# ToolManger-15ports-schematic.net
KiCad netlist of a schematic drawn in EAGLE
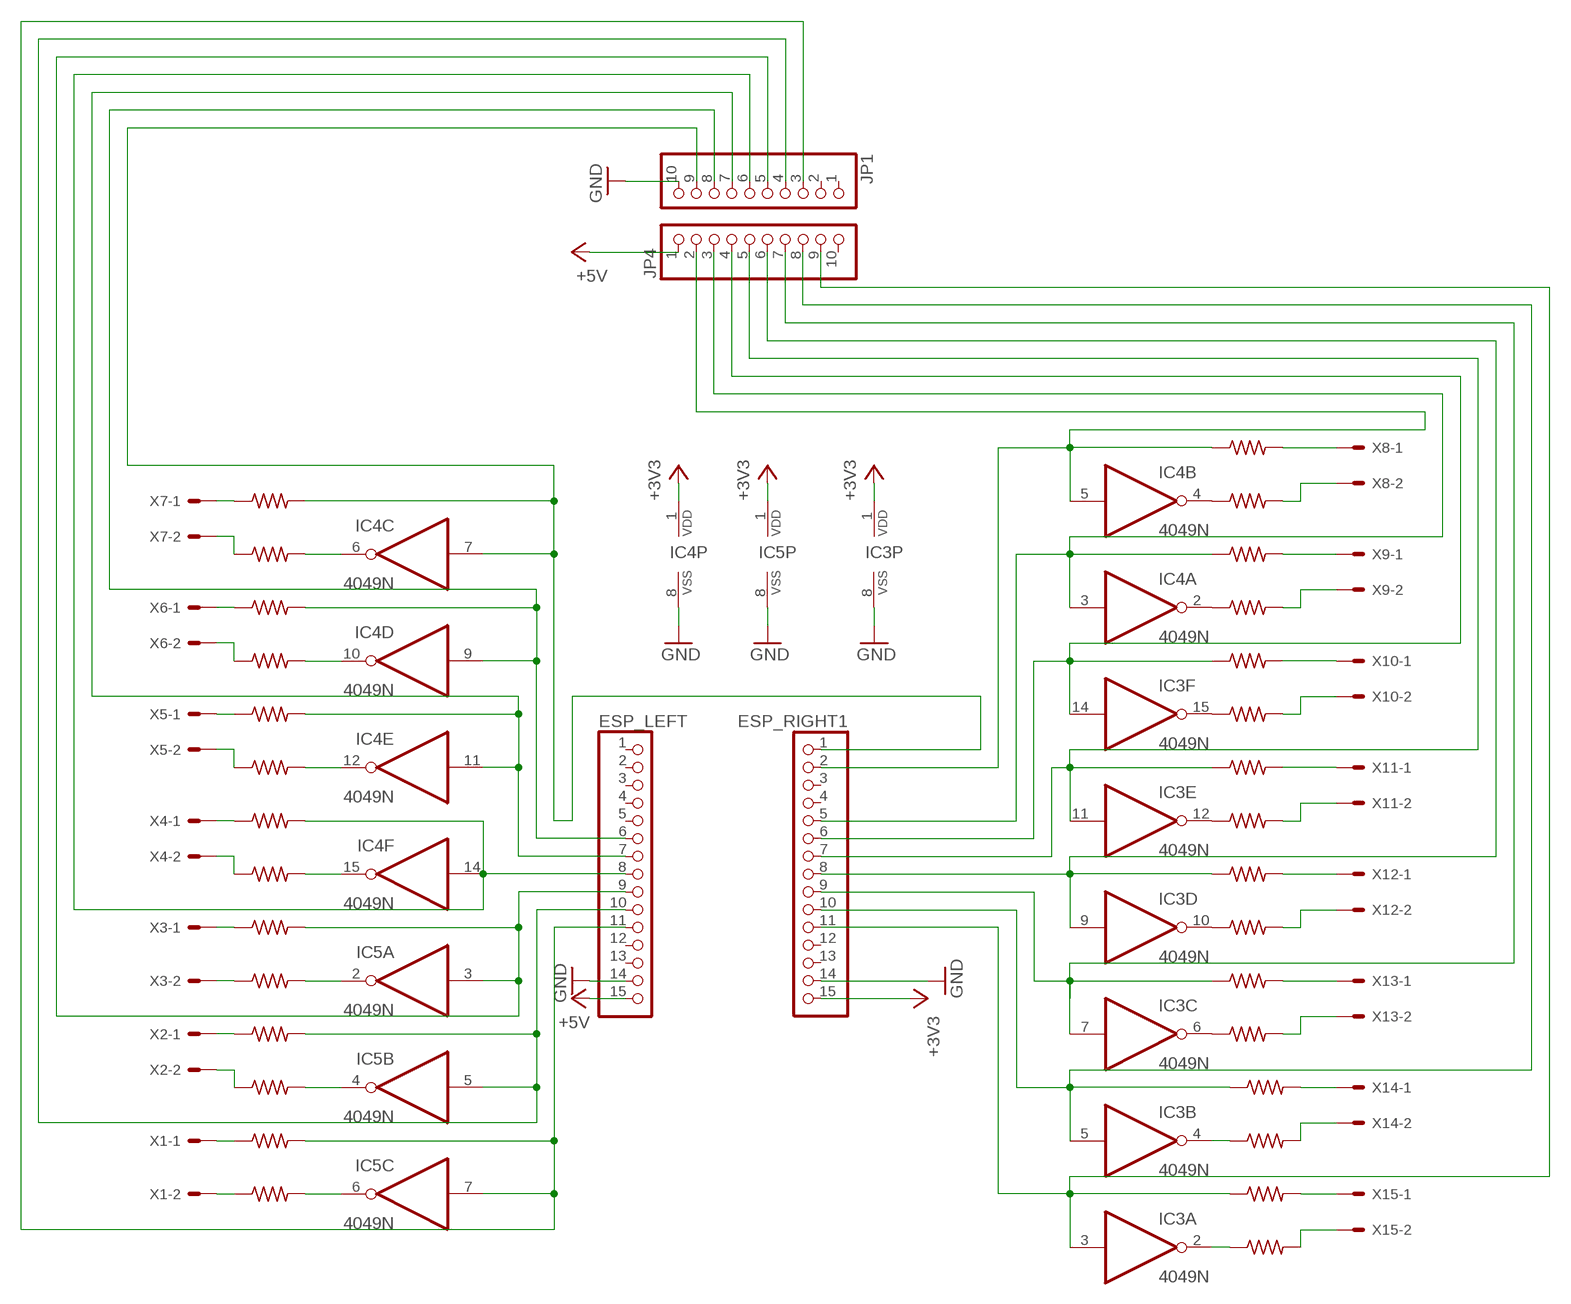
[diagram p0: schematic, sheet 1]

(export (version "E")
  (design (tool "Eeschema 10.0.6"))
  (components
    (comp (ref "ESP_LEFT")
      (value "PINHD-1X15")
      (footprint "eagle-import:1X15")
      (libsource (lib "eagle-import") (part "PINHD-1X15"))
    )
    (comp (ref "ESP_RIGHT1")
      (value "PINHD-1X15")
      (footprint "eagle-import:1X15")
      (libsource (lib "eagle-import") (part "PINHD-1X15"))
    )
    (comp (ref "IC3")
      (value "4049N")
      (footprint "eagle-import:DIL16")
      (libsource (lib "eagle-import") (part "4049N"))
    )
    (comp (ref "IC4")
      (value "4049N")
      (footprint "eagle-import:DIL16")
      (libsource (lib "eagle-import") (part "4049N"))
    )
    (comp (ref "IC5")
      (value "4049N")
      (footprint "eagle-import:DIL16")
      (libsource (lib "eagle-import") (part "4049N"))
    )
    (comp (ref "JP1")
      (value "PINHD-1X10")
      (footprint "eagle-import:1X10")
      (libsource (lib "eagle-import") (part "PINHD-1X10"))
    )
    (comp (ref "JP4")
      (value "PINHD-1X10")
      (footprint "eagle-import:1X10")
      (libsource (lib "eagle-import") (part "PINHD-1X10"))
    )
    (comp (ref "R1")
      (value "R-US_0207/12")
      (footprint "eagle-import:0207_12")
      (libsource (lib "eagle-import") (part "R-US_0207/12"))
    )
    (comp (ref "R2")
      (value "R-US_0207/12")
      (footprint "eagle-import:0207_12")
      (libsource (lib "eagle-import") (part "R-US_0207/12"))
    )
    (comp (ref "R3")
      (value "R-US_0207/12")
      (footprint "eagle-import:0207_12")
      (libsource (lib "eagle-import") (part "R-US_0207/12"))
    )
    (comp (ref "R4")
      (value "R-US_0207/12")
      (footprint "eagle-import:0207_12")
      (libsource (lib "eagle-import") (part "R-US_0207/12"))
    )
    (comp (ref "R5")
      (value "R-US_0207/12")
      (footprint "eagle-import:0207_12")
      (libsource (lib "eagle-import") (part "R-US_0207/12"))
    )
    (comp (ref "R6")
      (value "R-US_0207/12")
      (footprint "eagle-import:0207_12")
      (libsource (lib "eagle-import") (part "R-US_0207/12"))
    )
    (comp (ref "R7")
      (value "R-US_0207/12")
      (footprint "eagle-import:0207_12")
      (libsource (lib "eagle-import") (part "R-US_0207/12"))
    )
    (comp (ref "R8")
      (value "R-US_0207/12")
      (footprint "eagle-import:0207_12")
      (libsource (lib "eagle-import") (part "R-US_0207/12"))
    )
    (comp (ref "R9")
      (value "R-US_0207/12")
      (footprint "eagle-import:0207_12")
      (libsource (lib "eagle-import") (part "R-US_0207/12"))
    )
    (comp (ref "R10")
      (value "R-US_0207/12")
      (footprint "eagle-import:0207_12")
      (libsource (lib "eagle-import") (part "R-US_0207/12"))
    )
    (comp (ref "R11")
      (value "R-US_0207/12")
      (footprint "eagle-import:0207_12")
      (libsource (lib "eagle-import") (part "R-US_0207/12"))
    )
    (comp (ref "R12")
      (value "R-US_0207/12")
      (footprint "eagle-import:0207_12")
      (libsource (lib "eagle-import") (part "R-US_0207/12"))
    )
    (comp (ref "R13")
      (value "R-US_0207/12")
      (footprint "eagle-import:0207_12")
      (libsource (lib "eagle-import") (part "R-US_0207/12"))
    )
    (comp (ref "R14")
      (value "R-US_0207/12")
      (footprint "eagle-import:0207_12")
      (libsource (lib "eagle-import") (part "R-US_0207/12"))
    )
    (comp (ref "R15")
      (value "R-US_0207/12")
      (footprint "eagle-import:0207_12")
      (libsource (lib "eagle-import") (part "R-US_0207/12"))
    )
    (comp (ref "R16")
      (value "R-US_0207/12")
      (footprint "eagle-import:0207_12")
      (libsource (lib "eagle-import") (part "R-US_0207/12"))
    )
    (comp (ref "R17")
      (value "R-US_0207/12")
      (footprint "eagle-import:0207_12")
      (libsource (lib "eagle-import") (part "R-US_0207/12"))
    )
    (comp (ref "R18")
      (value "R-US_0207/12")
      (footprint "eagle-import:0207_12")
      (libsource (lib "eagle-import") (part "R-US_0207/12"))
    )
    (comp (ref "R19")
      (value "R-US_0207/12")
      (footprint "eagle-import:0207_12")
      (libsource (lib "eagle-import") (part "R-US_0207/12"))
    )
    (comp (ref "R21")
      (value "R-US_0207/12")
      (footprint "eagle-import:0207_12")
      (libsource (lib "eagle-import") (part "R-US_0207/12"))
    )
    (comp (ref "R22")
      (value "R-US_0207/12")
      (footprint "eagle-import:0207_12")
      (libsource (lib "eagle-import") (part "R-US_0207/12"))
    )
    (comp (ref "R23")
      (value "R-US_0207/12")
      (footprint "eagle-import:0207_12")
      (libsource (lib "eagle-import") (part "R-US_0207/12"))
    )
    (comp (ref "R24")
      (value "R-US_0207/12")
      (footprint "eagle-import:0207_12")
      (libsource (lib "eagle-import") (part "R-US_0207/12"))
    )
    (comp (ref "R25")
      (value "R-US_0207/12")
      (footprint "eagle-import:0207_12")
      (libsource (lib "eagle-import") (part "R-US_0207/12"))
    )
    (comp (ref "R26")
      (value "R-US_0207/12")
      (footprint "eagle-import:0207_12")
      (libsource (lib "eagle-import") (part "R-US_0207/12"))
    )
    (comp (ref "R27")
      (value "R-US_0207/12")
      (footprint "eagle-import:0207_12")
      (libsource (lib "eagle-import") (part "R-US_0207/12"))
    )
    (comp (ref "R28")
      (value "R-US_0207/12")
      (footprint "eagle-import:0207_12")
      (libsource (lib "eagle-import") (part "R-US_0207/12"))
    )
    (comp (ref "R29")
      (value "R-US_0207/12")
      (footprint "eagle-import:0207_12")
      (libsource (lib "eagle-import") (part "R-US_0207/12"))
    )
    (comp (ref "R30")
      (value "R-US_0207/12")
      (footprint "eagle-import:0207_12")
      (libsource (lib "eagle-import") (part "R-US_0207/12"))
    )
    (comp (ref "R32")
      (value "R-US_0207/12")
      (footprint "eagle-import:0207_12")
      (libsource (lib "eagle-import") (part "R-US_0207/12"))
    )
    (comp (ref "X1")
      (value "KK-156-2")
      (footprint "eagle-import:KK-156-2")
      (fields (field (name "MF") "MOLEX"))
      (libsource (lib "eagle-import") (part "KK-156-2"))
    )
    (comp (ref "X2")
      (value "KK-156-2")
      (footprint "eagle-import:KK-156-2")
      (fields (field (name "MF") "MOLEX"))
      (libsource (lib "eagle-import") (part "KK-156-2"))
    )
    (comp (ref "X3")
      (value "KK-156-2")
      (footprint "eagle-import:KK-156-2")
      (fields (field (name "MF") "MOLEX"))
      (libsource (lib "eagle-import") (part "KK-156-2"))
    )
    (comp (ref "X4")
      (value "KK-156-2")
      (footprint "eagle-import:KK-156-2")
      (fields (field (name "MF") "MOLEX"))
      (libsource (lib "eagle-import") (part "KK-156-2"))
    )
    (comp (ref "X5")
      (value "KK-156-2")
      (footprint "eagle-import:KK-156-2")
      (fields (field (name "MF") "MOLEX"))
      (libsource (lib "eagle-import") (part "KK-156-2"))
    )
    (comp (ref "X6")
      (value "KK-156-2")
      (footprint "eagle-import:KK-156-2")
      (fields (field (name "MF") "MOLEX"))
      (libsource (lib "eagle-import") (part "KK-156-2"))
    )
    (comp (ref "X7")
      (value "KK-156-2")
      (footprint "eagle-import:KK-156-2")
      (fields (field (name "MF") "MOLEX"))
      (libsource (lib "eagle-import") (part "KK-156-2"))
    )
    (comp (ref "X8")
      (value "KK-156-2")
      (footprint "eagle-import:KK-156-2")
      (fields (field (name "MF") "MOLEX"))
      (libsource (lib "eagle-import") (part "KK-156-2"))
    )
    (comp (ref "X9")
      (value "KK-156-2")
      (footprint "eagle-import:KK-156-2")
      (fields (field (name "MF") "MOLEX"))
      (libsource (lib "eagle-import") (part "KK-156-2"))
    )
    (comp (ref "X10")
      (value "KK-156-2")
      (footprint "eagle-import:KK-156-2")
      (fields (field (name "MF") "MOLEX"))
      (libsource (lib "eagle-import") (part "KK-156-2"))
    )
    (comp (ref "X11")
      (value "KK-156-2")
      (footprint "eagle-import:KK-156-2")
      (fields (field (name "MF") "MOLEX"))
      (libsource (lib "eagle-import") (part "KK-156-2"))
    )
    (comp (ref "X12")
      (value "KK-156-2")
      (footprint "eagle-import:KK-156-2")
      (fields (field (name "MF") "MOLEX"))
      (libsource (lib "eagle-import") (part "KK-156-2"))
    )
    (comp (ref "X13")
      (value "KK-156-2")
      (footprint "eagle-import:KK-156-2")
      (fields (field (name "MF") "MOLEX"))
      (libsource (lib "eagle-import") (part "KK-156-2"))
    )
    (comp (ref "X14")
      (value "KK-156-2")
      (footprint "eagle-import:KK-156-2")
      (fields (field (name "MF") "MOLEX"))
      (libsource (lib "eagle-import") (part "KK-156-2"))
    )
    (comp (ref "X15")
      (value "KK-156-2")
      (footprint "eagle-import:KK-156-2")
      (fields (field (name "MF") "MOLEX"))
      (libsource (lib "eagle-import") (part "KK-156-2"))
    )
  )
  (nets
    (net (code "1") (name "+3V3") (class "Default")
      (node (ref "ESP_RIGHT1") (pin "15") (pinfunction "15_15") (pintype "passive"))
      (node (ref "IC3") (pin "1") (pinfunction "VDD_1") (pintype "power_in"))
      (node (ref "IC4") (pin "1") (pinfunction "VDD_1") (pintype "power_in"))
      (node (ref "IC5") (pin "1") (pinfunction "VDD_1") (pintype "power_in"))
    )
    (net (code "2") (name "+5V") (class "Default")
      (node (ref "ESP_LEFT") (pin "15") (pinfunction "15_15") (pintype "passive"))
      (node (ref "JP4") (pin "1") (pinfunction "1_1") (pintype "passive"))
    )
    (net (code "3") (name "GND") (class "Default")
      (node (ref "ESP_LEFT") (pin "14") (pinfunction "14_14") (pintype "passive"))
      (node (ref "ESP_RIGHT1") (pin "14") (pinfunction "14_14") (pintype "passive"))
      (node (ref "IC3") (pin "8") (pinfunction "VSS_8") (pintype "power_in"))
      (node (ref "IC4") (pin "8") (pinfunction "VSS_8") (pintype "power_in"))
      (node (ref "IC5") (pin "8") (pinfunction "VSS_8") (pintype "power_in"))
      (node (ref "JP1") (pin "10") (pinfunction "10_10") (pintype "passive"))
    )
    (net (code "4") (name "Net-(IC3A-I)") (class "Default")
      (node (ref "ESP_RIGHT1") (pin "11") (pinfunction "11_11") (pintype "passive"))
      (node (ref "IC3") (pin "3") (pinfunction "I_3") (pintype "input"))
      (node (ref "JP4") (pin "9") (pinfunction "9_9") (pintype "passive"))
      (node (ref "R1") (pin "1") (pinfunction "1_1") (pintype "passive"))
    )
    (net (code "5") (name "Net-(IC3A-O)") (class "Default")
      (node (ref "IC3") (pin "2") (pinfunction "O_2") (pintype "output"))
      (node (ref "R6") (pin "1") (pinfunction "1_1") (pintype "passive"))
    )
    (net (code "6") (name "Net-(IC3B-I)") (class "Default")
      (node (ref "ESP_RIGHT1") (pin "10") (pinfunction "10_10") (pintype "passive"))
      (node (ref "IC3") (pin "5") (pinfunction "I_5") (pintype "input"))
      (node (ref "JP4") (pin "8") (pinfunction "8_8") (pintype "passive"))
      (node (ref "R3") (pin "1") (pinfunction "1_1") (pintype "passive"))
    )
    (net (code "7") (name "Net-(IC3B-O)") (class "Default")
      (node (ref "IC3") (pin "4") (pinfunction "O_4") (pintype "output"))
      (node (ref "R2") (pin "1") (pinfunction "1_1") (pintype "passive"))
    )
    (net (code "8") (name "Net-(IC3C-I)") (class "Default")
      (node (ref "ESP_RIGHT1") (pin "9") (pinfunction "9_9") (pintype "passive"))
      (node (ref "IC3") (pin "7") (pinfunction "I_7") (pintype "input"))
      (node (ref "JP4") (pin "7") (pinfunction "7_7") (pintype "passive"))
      (node (ref "R5") (pin "1") (pinfunction "1_1") (pintype "passive"))
    )
    (net (code "9") (name "Net-(IC3C-O)") (class "Default")
      (node (ref "IC3") (pin "6") (pinfunction "O_6") (pintype "output"))
      (node (ref "R4") (pin "1") (pinfunction "1_1") (pintype "passive"))
    )
    (net (code "10") (name "Net-(IC3D-I)") (class "Default")
      (node (ref "ESP_RIGHT1") (pin "8") (pinfunction "8_8") (pintype "passive"))
      (node (ref "IC3") (pin "9") (pinfunction "I_9") (pintype "input"))
      (node (ref "JP4") (pin "6") (pinfunction "6_6") (pintype "passive"))
      (node (ref "R8") (pin "1") (pinfunction "1_1") (pintype "passive"))
    )
    (net (code "11") (name "Net-(IC3D-O)") (class "Default")
      (node (ref "IC3") (pin "10") (pinfunction "O_10") (pintype "output"))
      (node (ref "R7") (pin "1") (pinfunction "1_1") (pintype "passive"))
    )
    (net (code "12") (name "Net-(IC3E-I)") (class "Default")
      (node (ref "ESP_RIGHT1") (pin "7") (pinfunction "7_7") (pintype "passive"))
      (node (ref "IC3") (pin "11") (pinfunction "I_11") (pintype "input"))
      (node (ref "JP4") (pin "5") (pinfunction "5_5") (pintype "passive"))
      (node (ref "R10") (pin "1") (pinfunction "1_1") (pintype "passive"))
    )
    (net (code "13") (name "Net-(IC3E-O)") (class "Default")
      (node (ref "IC3") (pin "12") (pinfunction "O_12") (pintype "output"))
      (node (ref "R9") (pin "1") (pinfunction "1_1") (pintype "passive"))
    )
    (net (code "14") (name "Net-(IC3F-I)") (class "Default")
      (node (ref "ESP_RIGHT1") (pin "6") (pinfunction "6_6") (pintype "passive"))
      (node (ref "IC3") (pin "14") (pinfunction "I_14") (pintype "input"))
      (node (ref "JP4") (pin "4") (pinfunction "4_4") (pintype "passive"))
      (node (ref "R12") (pin "1") (pinfunction "1_1") (pintype "passive"))
    )
    (net (code "15") (name "Net-(IC3F-O)") (class "Default")
      (node (ref "IC3") (pin "15") (pinfunction "O_15") (pintype "output"))
      (node (ref "R11") (pin "1") (pinfunction "1_1") (pintype "passive"))
    )
    (net (code "16") (name "Net-(IC4A-I)") (class "Default")
      (node (ref "ESP_RIGHT1") (pin "5") (pinfunction "5_5") (pintype "passive"))
      (node (ref "IC4") (pin "3") (pinfunction "I_3") (pintype "input"))
      (node (ref "JP4") (pin "3") (pinfunction "3_3") (pintype "passive"))
      (node (ref "R14") (pin "1") (pinfunction "1_1") (pintype "passive"))
    )
    (net (code "17") (name "Net-(IC4A-O)") (class "Default")
      (node (ref "IC4") (pin "2") (pinfunction "O_2") (pintype "output"))
      (node (ref "R13") (pin "1") (pinfunction "1_1") (pintype "passive"))
    )
    (net (code "18") (name "Net-(IC4B-I)") (class "Default")
      (node (ref "ESP_RIGHT1") (pin "2") (pinfunction "2_2") (pintype "passive"))
      (node (ref "IC4") (pin "5") (pinfunction "I_5") (pintype "input"))
      (node (ref "JP4") (pin "2") (pinfunction "2_2") (pintype "passive"))
      (node (ref "R16") (pin "1") (pinfunction "1_1") (pintype "passive"))
    )
    (net (code "19") (name "Net-(IC4B-O)") (class "Default")
      (node (ref "IC4") (pin "4") (pinfunction "O_4") (pintype "output"))
      (node (ref "R15") (pin "1") (pinfunction "1_1") (pintype "passive"))
    )
    (net (code "20") (name "Net-(IC4C-I)") (class "Default")
      (node (ref "ESP_RIGHT1") (pin "1") (pinfunction "1_1") (pintype "passive"))
      (node (ref "IC4") (pin "7") (pinfunction "I_7") (pintype "input"))
      (node (ref "JP1") (pin "9") (pinfunction "9_9") (pintype "passive"))
      (node (ref "R32") (pin "2") (pinfunction "2_2") (pintype "passive"))
    )
    (net (code "21") (name "Net-(IC4C-O)") (class "Default")
      (node (ref "IC4") (pin "6") (pinfunction "O_6") (pintype "output"))
      (node (ref "R19") (pin "2") (pinfunction "2_2") (pintype "passive"))
    )
    (net (code "22") (name "Net-(IC4D-I)") (class "Default")
      (node (ref "ESP_LEFT") (pin "6") (pinfunction "6_6") (pintype "passive"))
      (node (ref "IC4") (pin "9") (pinfunction "I_9") (pintype "input"))
      (node (ref "JP1") (pin "8") (pinfunction "8_8") (pintype "passive"))
      (node (ref "R30") (pin "2") (pinfunction "2_2") (pintype "passive"))
    )
    (net (code "23") (name "Net-(IC4D-O)") (class "Default")
      (node (ref "IC4") (pin "10") (pinfunction "O_10") (pintype "output"))
      (node (ref "R29") (pin "2") (pinfunction "2_2") (pintype "passive"))
    )
    (net (code "24") (name "Net-(IC4E-I)") (class "Default")
      (node (ref "ESP_LEFT") (pin "7") (pinfunction "7_7") (pintype "passive"))
      (node (ref "IC4") (pin "11") (pinfunction "I_11") (pintype "input"))
      (node (ref "JP1") (pin "7") (pinfunction "7_7") (pintype "passive"))
      (node (ref "R18") (pin "2") (pinfunction "2_2") (pintype "passive"))
    )
    (net (code "25") (name "Net-(IC4E-O)") (class "Default")
      (node (ref "IC4") (pin "12") (pinfunction "O_12") (pintype "output"))
      (node (ref "R28") (pin "2") (pinfunction "2_2") (pintype "passive"))
    )
    (net (code "26") (name "Net-(IC4F-I)") (class "Default")
      (node (ref "ESP_LEFT") (pin "8") (pinfunction "8_8") (pintype "passive"))
      (node (ref "IC4") (pin "14") (pinfunction "I_14") (pintype "input"))
      (node (ref "JP1") (pin "6") (pinfunction "6_6") (pintype "passive"))
      (node (ref "R27") (pin "2") (pinfunction "2_2") (pintype "passive"))
    )
    (net (code "27") (name "Net-(IC4F-O)") (class "Default")
      (node (ref "IC4") (pin "15") (pinfunction "O_15") (pintype "output"))
      (node (ref "R26") (pin "2") (pinfunction "2_2") (pintype "passive"))
    )
    (net (code "28") (name "Net-(IC5A-I)") (class "Default")
      (node (ref "ESP_LEFT") (pin "9") (pinfunction "9_9") (pintype "passive"))
      (node (ref "IC5") (pin "3") (pinfunction "I_3") (pintype "input"))
      (node (ref "JP1") (pin "5") (pinfunction "5_5") (pintype "passive"))
      (node (ref "R25") (pin "2") (pinfunction "2_2") (pintype "passive"))
    )
    (net (code "29") (name "Net-(IC5A-O)") (class "Default")
      (node (ref "IC5") (pin "2") (pinfunction "O_2") (pintype "output"))
      (node (ref "R24") (pin "2") (pinfunction "2_2") (pintype "passive"))
    )
    (net (code "30") (name "Net-(IC5B-I)") (class "Default")
      (node (ref "ESP_LEFT") (pin "10") (pinfunction "10_10") (pintype "passive"))
      (node (ref "IC5") (pin "5") (pinfunction "I_5") (pintype "input"))
      (node (ref "JP1") (pin "4") (pinfunction "4_4") (pintype "passive"))
      (node (ref "R23") (pin "2") (pinfunction "2_2") (pintype "passive"))
    )
    (net (code "31") (name "Net-(IC5B-O)") (class "Default")
      (node (ref "IC5") (pin "4") (pinfunction "O_4") (pintype "output"))
      (node (ref "R22") (pin "2") (pinfunction "2_2") (pintype "passive"))
    )
    (net (code "32") (name "Net-(IC5C-I)") (class "Default")
      (node (ref "ESP_LEFT") (pin "11") (pinfunction "11_11") (pintype "passive"))
      (node (ref "IC5") (pin "7") (pinfunction "I_7") (pintype "input"))
      (node (ref "JP1") (pin "3") (pinfunction "3_3") (pintype "passive"))
      (node (ref "R21") (pin "2") (pinfunction "2_2") (pintype "passive"))
    )
    (net (code "33") (name "Net-(IC5C-O)") (class "Default")
      (node (ref "IC5") (pin "6") (pinfunction "O_6") (pintype "output"))
      (node (ref "R17") (pin "2") (pinfunction "2_2") (pintype "passive"))
    )
    (net (code "34") (name "Net-(X1A-S)") (class "Default")
      (node (ref "R21") (pin "1") (pinfunction "1_1") (pintype "passive"))
      (node (ref "X1") (pin "1") (pinfunction "S_1") (pintype "passive"))
    )
    (net (code "35") (name "Net-(X1B-S)") (class "Default")
      (node (ref "R17") (pin "1") (pinfunction "1_1") (pintype "passive"))
      (node (ref "X1") (pin "2") (pinfunction "S_2") (pintype "passive"))
    )
    (net (code "36") (name "Net-(X2A-S)") (class "Default")
      (node (ref "R23") (pin "1") (pinfunction "1_1") (pintype "passive"))
      (node (ref "X2") (pin "1") (pinfunction "S_1") (pintype "passive"))
    )
    (net (code "37") (name "Net-(X2B-S)") (class "Default")
      (node (ref "R22") (pin "1") (pinfunction "1_1") (pintype "passive"))
      (node (ref "X2") (pin "2") (pinfunction "S_2") (pintype "passive"))
    )
    (net (code "38") (name "Net-(X3A-S)") (class "Default")
      (node (ref "R25") (pin "1") (pinfunction "1_1") (pintype "passive"))
      (node (ref "X3") (pin "1") (pinfunction "S_1") (pintype "passive"))
    )
    (net (code "39") (name "Net-(X3B-S)") (class "Default")
      (node (ref "R24") (pin "1") (pinfunction "1_1") (pintype "passive"))
      (node (ref "X3") (pin "2") (pinfunction "S_2") (pintype "passive"))
    )
    (net (code "40") (name "Net-(X4A-S)") (class "Default")
      (node (ref "R27") (pin "1") (pinfunction "1_1") (pintype "passive"))
      (node (ref "X4") (pin "1") (pinfunction "S_1") (pintype "passive"))
    )
    (net (code "41") (name "Net-(X4B-S)") (class "Default")
      (node (ref "R26") (pin "1") (pinfunction "1_1") (pintype "passive"))
      (node (ref "X4") (pin "2") (pinfunction "S_2") (pintype "passive"))
    )
    (net (code "42") (name "Net-(X5A-S)") (class "Default")
      (node (ref "R18") (pin "1") (pinfunction "1_1") (pintype "passive"))
      (node (ref "X5") (pin "1") (pinfunction "S_1") (pintype "passive"))
    )
    (net (code "43") (name "Net-(X5B-S)") (class "Default")
      (node (ref "R28") (pin "1") (pinfunction "1_1") (pintype "passive"))
      (node (ref "X5") (pin "2") (pinfunction "S_2") (pintype "passive"))
    )
    (net (code "44") (name "Net-(X6A-S)") (class "Default")
      (node (ref "R30") (pin "1") (pinfunction "1_1") (pintype "passive"))
      (node (ref "X6") (pin "1") (pinfunction "S_1") (pintype "passive"))
    )
    (net (code "45") (name "Net-(X6B-S)") (class "Default")
      (node (ref "R29") (pin "1") (pinfunction "1_1") (pintype "passive"))
      (node (ref "X6") (pin "2") (pinfunction "S_2") (pintype "passive"))
    )
    (net (code "46") (name "Net-(X7A-S)") (class "Default")
      (node (ref "R32") (pin "1") (pinfunction "1_1") (pintype "passive"))
      (node (ref "X7") (pin "1") (pinfunction "S_1") (pintype "passive"))
    )
    (net (code "47") (name "Net-(X7B-S)") (class "Default")
      (node (ref "R19") (pin "1") (pinfunction "1_1") (pintype "passive"))
      (node (ref "X7") (pin "2") (pinfunction "S_2") (pintype "passive"))
    )
    (net (code "48") (name "Net-(X8A-S)") (class "Default")
      (node (ref "R16") (pin "2") (pinfunction "2_2") (pintype "passive"))
      (node (ref "X8") (pin "1") (pinfunction "S_1") (pintype "passive"))
    )
    (net (code "49") (name "Net-(X8B-S)") (class "Default")
      (node (ref "R15") (pin "2") (pinfunction "2_2") (pintype "passive"))
      (node (ref "X8") (pin "2") (pinfunction "S_2") (pintype "passive"))
    )
    (net (code "50") (name "Net-(X9A-S)") (class "Default")
      (node (ref "R14") (pin "2") (pinfunction "2_2") (pintype "passive"))
      (node (ref "X9") (pin "1") (pinfunction "S_1") (pintype "passive"))
    )
    (net (code "51") (name "Net-(X9B-S)") (class "Default")
      (node (ref "R13") (pin "2") (pinfunction "2_2") (pintype "passive"))
      (node (ref "X9") (pin "2") (pinfunction "S_2") (pintype "passive"))
    )
    (net (code "52") (name "Net-(X10A-S)") (class "Default")
      (node (ref "R12") (pin "2") (pinfunction "2_2") (pintype "passive"))
      (node (ref "X10") (pin "1") (pinfunction "S_1") (pintype "passive"))
    )
    (net (code "53") (name "Net-(X10B-S)") (class "Default")
      (node (ref "R11") (pin "2") (pinfunction "2_2") (pintype "passive"))
      (node (ref "X10") (pin "2") (pinfunction "S_2") (pintype "passive"))
    )
    (net (code "54") (name "Net-(X11A-S)") (class "Default")
      (node (ref "R10") (pin "2") (pinfunction "2_2") (pintype "passive"))
      (node (ref "X11") (pin "1") (pinfunction "S_1") (pintype "passive"))
    )
    (net (code "55") (name "Net-(X11B-S)") (class "Default")
      (node (ref "R9") (pin "2") (pinfunction "2_2") (pintype "passive"))
      (node (ref "X11") (pin "2") (pinfunction "S_2") (pintype "passive"))
    )
    (net (code "56") (name "Net-(X12A-S)") (class "Default")
      (node (ref "R8") (pin "2") (pinfunction "2_2") (pintype "passive"))
      (node (ref "X12") (pin "1") (pinfunction "S_1") (pintype "passive"))
    )
    (net (code "57") (name "Net-(X12B-S)") (class "Default")
      (node (ref "R7") (pin "2") (pinfunction "2_2") (pintype "passive"))
      (node (ref "X12") (pin "2") (pinfunction "S_2") (pintype "passive"))
    )
    (net (code "58") (name "Net-(X13A-S)") (class "Default")
      (node (ref "R5") (pin "2") (pinfunction "2_2") (pintype "passive"))
      (node (ref "X13") (pin "1") (pinfunction "S_1") (pintype "passive"))
    )
    (net (code "59") (name "Net-(X13B-S)") (class "Default")
      (node (ref "R4") (pin "2") (pinfunction "2_2") (pintype "passive"))
      (node (ref "X13") (pin "2") (pinfunction "S_2") (pintype "passive"))
    )
    (net (code "60") (name "Net-(X14A-S)") (class "Default")
      (node (ref "R3") (pin "2") (pinfunction "2_2") (pintype "passive"))
      (node (ref "X14") (pin "1") (pinfunction "S_1") (pintype "passive"))
    )
    (net (code "61") (name "Net-(X14B-S)") (class "Default")
      (node (ref "R2") (pin "2") (pinfunction "2_2") (pintype "passive"))
      (node (ref "X14") (pin "2") (pinfunction "S_2") (pintype "passive"))
    )
    (net (code "62") (name "Net-(X15A-S)") (class "Default")
      (node (ref "R1") (pin "2") (pinfunction "2_2") (pintype "passive"))
      (node (ref "X15") (pin "1") (pinfunction "S_1") (pintype "passive"))
    )
    (net (code "63") (name "Net-(X15B-S)") (class "Default")
      (node (ref "R6") (pin "2") (pinfunction "2_2") (pintype "passive"))
      (node (ref "X15") (pin "2") (pinfunction "S_2") (pintype "passive"))
    )
    (net (code "64") (name "unconnected-(ESP_LEFT-Pad1)") (class "Default")
      (node (ref "ESP_LEFT") (pin "1") (pinfunction "1_1") (pintype "passive"))
    )
    (net (code "65") (name "unconnected-(ESP_LEFT-Pad2)") (class "Default")
      (node (ref "ESP_LEFT") (pin "2") (pinfunction "2_2") (pintype "passive"))
    )
    (net (code "66") (name "unconnected-(ESP_LEFT-Pad3)") (class "Default")
      (node (ref "ESP_LEFT") (pin "3") (pinfunction "3_3") (pintype "passive"))
    )
    (net (code "67") (name "unconnected-(ESP_LEFT-Pad4)") (class "Default")
      (node (ref "ESP_LEFT") (pin "4") (pinfunction "4_4") (pintype "passive"))
    )
    (net (code "68") (name "unconnected-(ESP_LEFT-Pad5)") (class "Default")
      (node (ref "ESP_LEFT") (pin "5") (pinfunction "5_5") (pintype "passive"))
    )
    (net (code "69") (name "unconnected-(ESP_LEFT-Pad12)") (class "Default")
      (node (ref "ESP_LEFT") (pin "12") (pinfunction "12_12") (pintype "passive"))
    )
    (net (code "70") (name "unconnected-(ESP_LEFT-Pad13)") (class "Default")
      (node (ref "ESP_LEFT") (pin "13") (pinfunction "13_13") (pintype "passive"))
    )
    (net (code "71") (name "unconnected-(ESP_RIGHT1-Pad3)") (class "Default")
      (node (ref "ESP_RIGHT1") (pin "3") (pinfunction "3_3") (pintype "passive"))
    )
    (net (code "72") (name "unconnected-(ESP_RIGHT1-Pad4)") (class "Default")
      (node (ref "ESP_RIGHT1") (pin "4") (pinfunction "4_4") (pintype "passive"))
    )
    (net (code "73") (name "unconnected-(ESP_RIGHT1-Pad12)") (class "Default")
      (node (ref "ESP_RIGHT1") (pin "12") (pinfunction "12_12") (pintype "passive"))
    )
    (net (code "74") (name "unconnected-(ESP_RIGHT1-Pad13)") (class "Default")
      (node (ref "ESP_RIGHT1") (pin "13") (pinfunction "13_13") (pintype "passive"))
    )
    (net (code "75") (name "unconnected-(JP1-Pad1)") (class "Default")
      (node (ref "JP1") (pin "1") (pinfunction "1_1") (pintype "passive"))
    )
    (net (code "76") (name "unconnected-(JP1-Pad2)") (class "Default")
      (node (ref "JP1") (pin "2") (pinfunction "2_2") (pintype "passive"))
    )
    (net (code "77") (name "unconnected-(JP4-Pad10)") (class "Default")
      (node (ref "JP4") (pin "10") (pinfunction "10_10") (pintype "passive"))
    )
  )
)
